# POWER.net
KiCad netlist of a schematic drawn in Altium Designer
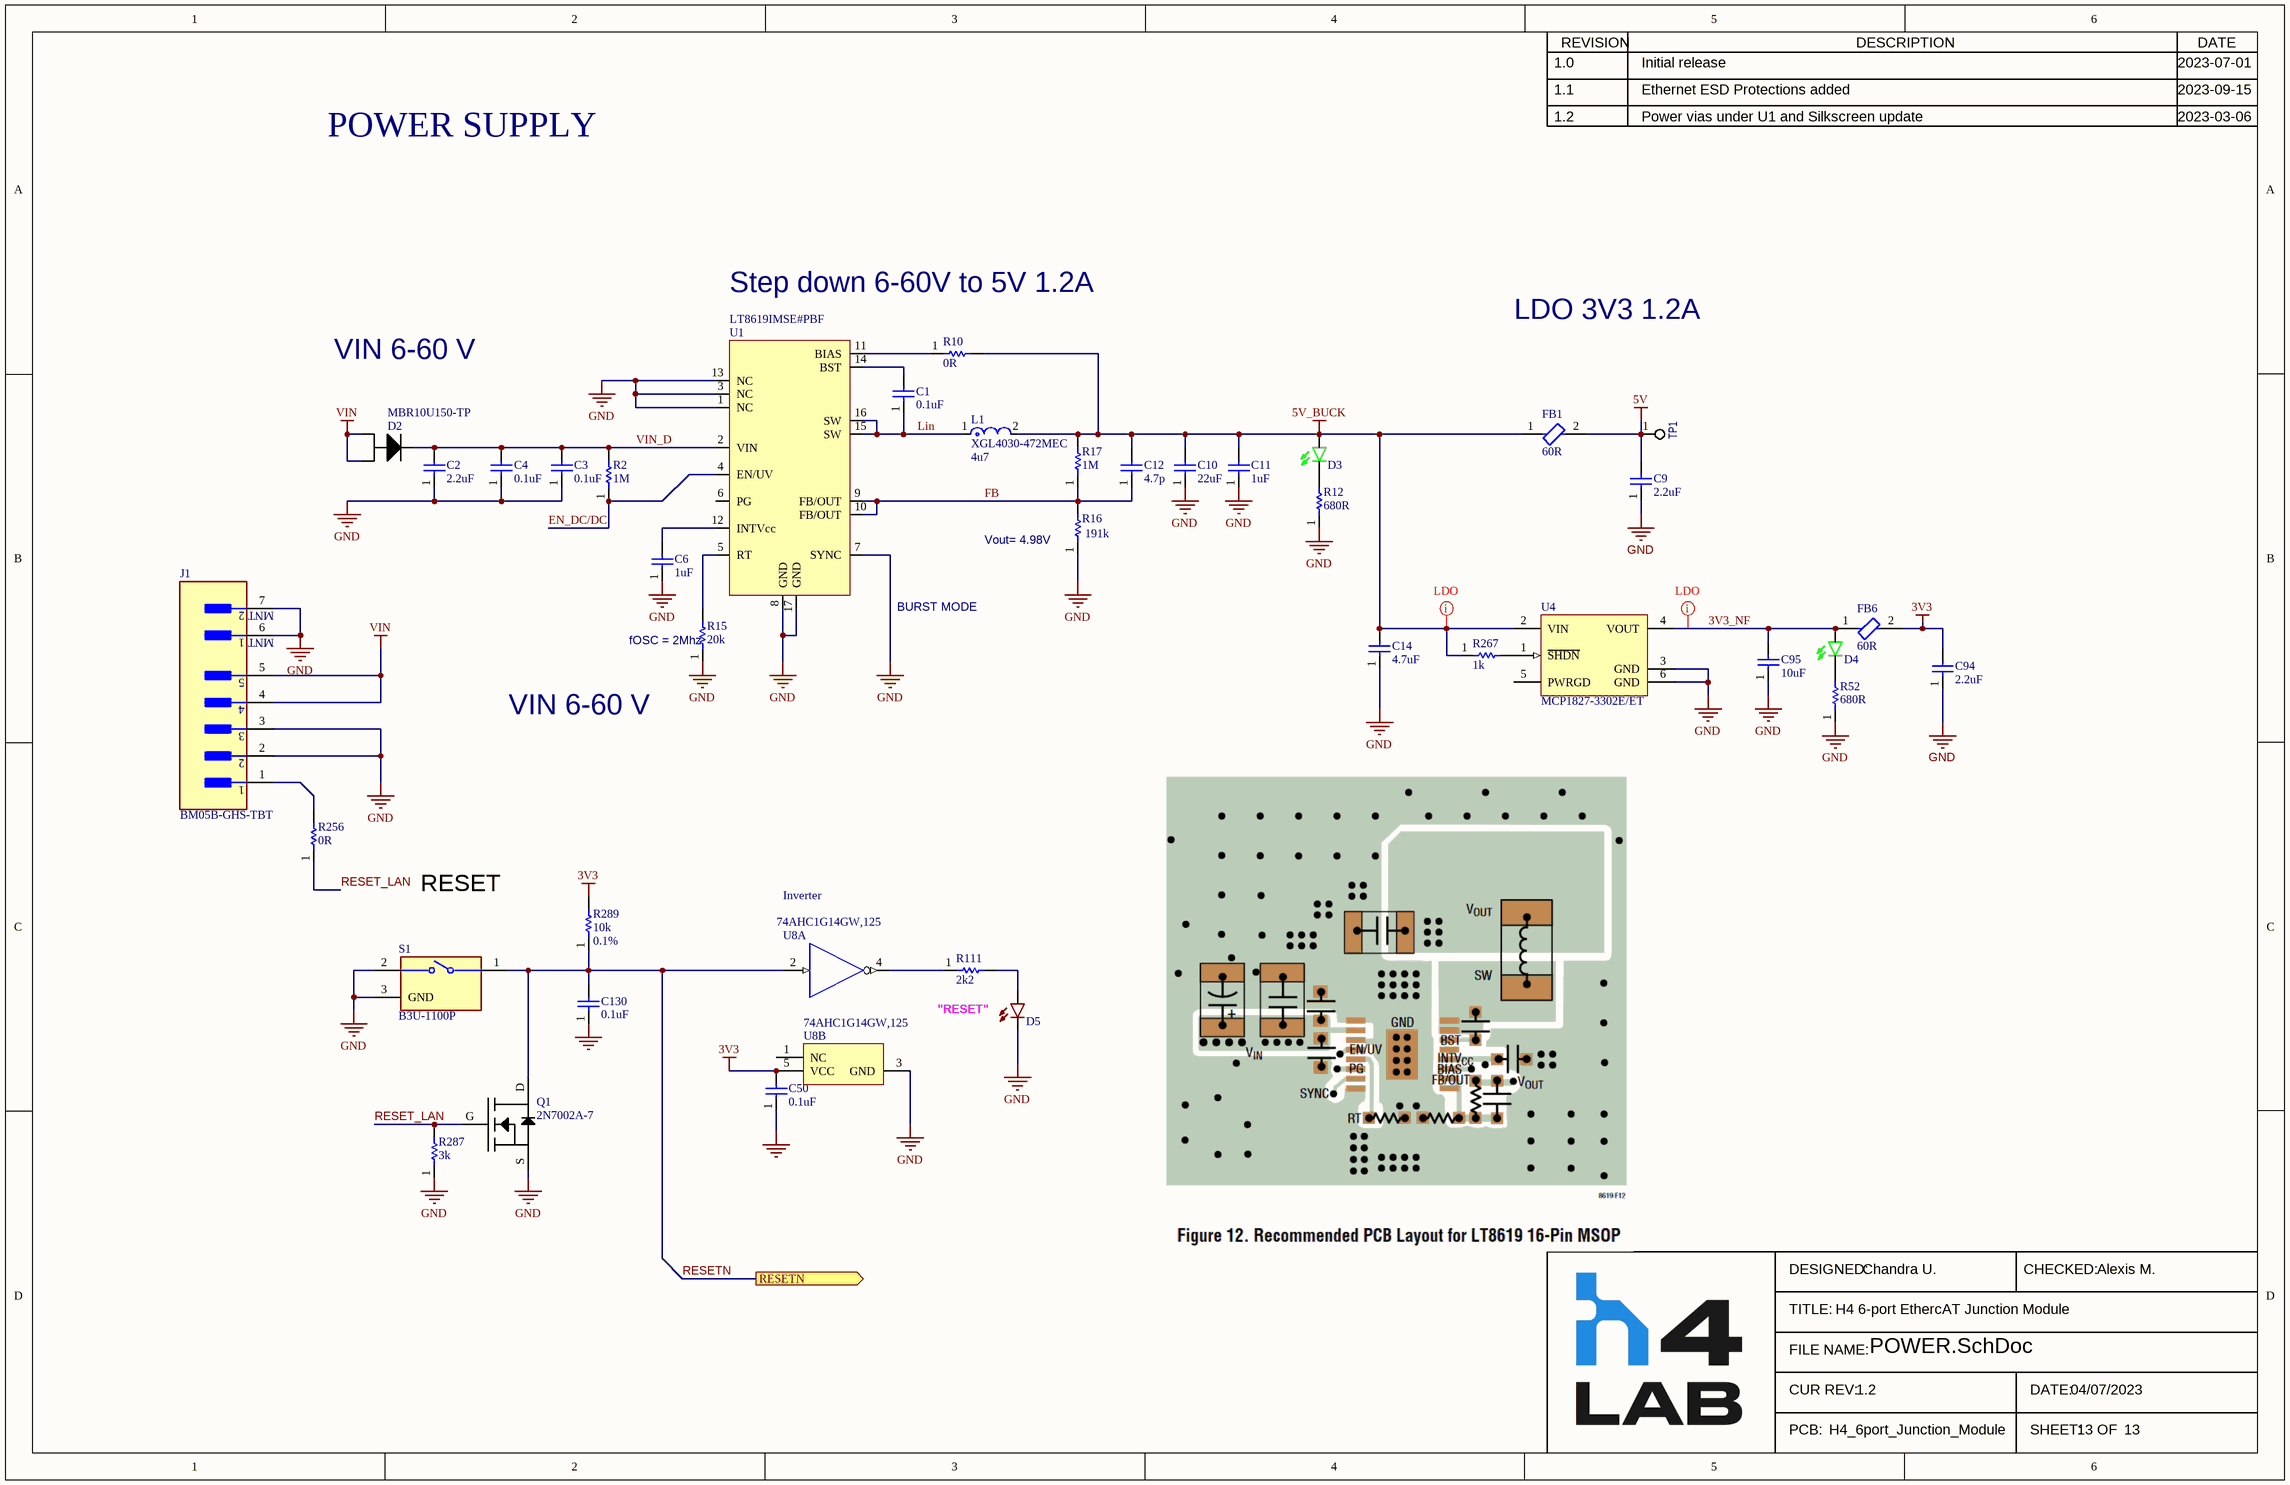
[diagram p0: POWER.SchDoc]

(export (version "E")
  (design (tool "Eeschema 10.0.6"))
  (components
    (comp (ref "C1")
      (value "0.1uF")
      (footprint "CAPC1608X09N(0603)")
      (description "CAP CER 0.1UF 100V X7R 0603")
      (fields (field (name "MPN") "CL10B104KC8NNNC") (field (name "TOLERANCE") "10%"))
      (libsource (lib "IHMC_Altium_Lib") (part "0.1uF_100V_0603_CAP"))
    )
    (comp (ref "C2")
      (value "2.2uF")
      (footprint "CAPC3216X16N(1206)")
      (description "CAP CER 2.2UF 100V X7S 1206")
      (fields (field (name "MPN") "C3216X7S2A225K160AB") (field (name "TOLERANCE") "10%"))
      (libsource (lib "IHMC_Altium_Lib") (part "2.2uF_100V_1206_Cap"))
    )
    (comp (ref "C3")
      (value "0.1uF")
      (footprint "CAPC1608X09N(0603)")
      (description "CAP CER 0.1UF 100V X7R 0603")
      (fields (field (name "MPN") "CL10B104KC8NNNC") (field (name "TOLERANCE") "10%"))
      (libsource (lib "IHMC_Altium_Lib") (part "0.1uF_100V_0603_CAP"))
    )
    (comp (ref "C4")
      (value "0.1uF")
      (footprint "CAPC1608X09N(0603)")
      (description "CAP CER 0.1UF 100V X7R 0603")
      (fields (field (name "MPN") "CL10B104KC8NNNC") (field (name "TOLERANCE") "10%"))
      (libsource (lib "IHMC_Altium_Lib") (part "0.1uF_100V_0603_CAP"))
    )
    (comp (ref "C6")
      (value "1uF")
      (footprint "CAPC1608X09N(0603)")
      (description "MLCC - SMD/SMT 25volts 1uF X5R 10%")
      (fields
        (field (name "MPN") "C0603C105K3PACTU")
        (field (name "VOLTAGE") "25VDC")
        (field (name "DRAWN BY") "TC")
      )
      (libsource (lib "IHMC_Altium_Lib") (part "1uF_25VDC_0603_Cap"))
    )
    (comp (ref "C9")
      (value "2.2uF")
      (footprint "CAPC1608X09N(0603)")
      (description "CAP CER 2.2UF 10V X5R 0603")
      (fields (field (name "MPN") "GRM188R61A225KE34D") (field (name "TOLERANCE") "10%"))
      (libsource (lib "IHMC_Altium_Lib") (part "2.2uF_10V_0603_CAP"))
    )
    (comp (ref "C10")
      (value "22uF")
      (footprint "CAPC1608X09N(0603)")
      (description "CAP CER 22UF 10V X5R 0603")
      (fields (field (name "MPN") "C1608X5R1A226M080AC") (field (name "TOLERANCE") "20%"))
      (libsource (lib "IHMC_Altium_Lib") (part "22uF_10V_0603_CAP"))
    )
    (comp (ref "C11")
      (value "1uF")
      (footprint "CAPC1608X09N(0603)")
      (description "MLCC - SMD/SMT 25volts 1uF X5R 10%")
      (fields
        (field (name "MPN") "C0603C105K3PACTU")
        (field (name "VOLTAGE") "25VDC")
        (field (name "DRAWN BY") "TC")
      )
      (libsource (lib "IHMC_Altium_Lib") (part "1uF_25VDC_0603_Cap"))
    )
    (comp (ref "C12")
      (value "4.7p")
      (footprint "0402_C")
      (fields
        (field (name "MANUFACTURER") "TDK")
        (field (name "MANUFACTURER PART NUMBER") "CGA2B2C0G1H4R7C050BA")
      )
      (libsource (lib "IHMC_Altium_Lib") (part "4p7_0402_50V_C0G_  CGA2B2C0G1H4R7C050BA"))
    )
    (comp (ref "C14")
      (value "4.7uF")
      (footprint "CAPC1608X09N(0603)")
      (description "CAP CER 4.7UF 10V X5R 0603")
      (fields (field (name "MPN") "CL10A475KP8NNNC"))
      (libsource (lib "IHMC_Altium_Lib") (part "4.7uF_10V_0603_CAP"))
    )
    (comp (ref "C50")
      (value "0.1uF")
      (footprint "CAPC1608X09N(0603)")
      (description "CAP CER 0.1UF 100V X7R 0603")
      (fields (field (name "MPN") "CL10B104KC8NNNC") (field (name "TOLERANCE") "10%"))
      (libsource (lib "IHMC_Altium_Lib") (part "0.1uF_100V_0603_CAP"))
    )
    (comp (ref "C94")
      (value "2.2uF")
      (footprint "CAPC1608X09N(0603)")
      (description "CAP CER 2.2UF 10V X5R 0603")
      (fields (field (name "MPN") "GRM188R61A225KE34D") (field (name "TOLERANCE") "10%"))
      (libsource (lib "IHMC_Altium_Lib") (part "2.2uF_10V_0603_CAP"))
    )
    (comp (ref "C95")
      (value "10uF")
      (footprint "CAPC3216X16N(1206)")
      (description "MLCC - SMD/SMT 1206 10uF 35volts")
      (fields
        (field (name "MPN") "GRM319R6YA106KA12D")
        (field (name "VOLTAGE") "35VDC")
        (field (name "DRAWN BY") "TC")
      )
      (libsource (lib "IHMC_Altium_Lib") (part "10uF_35VDC_1206_Cap"))
    )
    (comp (ref "C130")
      (value "0.1uF")
      (footprint "CAPC1608X09N(0603)")
      (description "CAP CER 0.1UF 100V X7R 0603")
      (fields (field (name "MPN") "CL10B104KC8NNNC") (field (name "TOLERANCE") "10%"))
      (libsource (lib "IHMC_Altium_Lib") (part "0.1uF_100V_0603_CAP"))
    )
    (comp (ref "D2")
      (value "MBR10U150-TP")
      (footprint "TO-277")
      (description "Diode Schottky 150V 10A TO277")
      (fields (field (name "MANUFACTURER") "MCC"))
      (libsource (lib "IHMC_Altium_Lib") (part "MBR10U150-TP_SCHOTTKY_150V_10A"))
    )
    (comp (ref "D3")
      (value "LTST-C193KGKT-5A")
      (footprint "LEDC1608X07N(0603)")
      (description "LED GREEN CLEAR CHIP SMD")
      (fields (field (name "DRAWN BY") "TC"))
      (libsource (lib "IHMC_Altium_Lib") (part "GREEN_LED_0603"))
    )
    (comp (ref "D4")
      (value "LTST-C193KGKT-5A")
      (footprint "LEDC1608X07N(0603)")
      (description "LED GREEN CLEAR CHIP SMD")
      (fields (field (name "DRAWN BY") "TC"))
      (libsource (lib "IHMC_Altium_Lib") (part "GREEN_LED_0603"))
    )
    (comp (ref "D5")
      (value "LTST-C193KRKT-5A")
      (footprint "LEDC1608X07N(0603)")
      (description "LED RED CLEAR CHIP SMD")
      (fields (field (name "DRAWN BY") "TC"))
      (libsource (lib "IHMC_Altium_Lib") (part "RED_LED_0603"))
    )
    (comp (ref "FB1")
      (value "BKP2125HS600-T")
      (footprint "FP-BKP2125-IPC_C")
      (fields
        (field (name "TOLERANCE") "25%")
        (field (name "MANUFACTURER") "Taiyo Yuden")
        (field (name "IMPEDANCE") "60R")
      )
      (libsource (lib "IHMC_Altium_Lib") (part "60R_100Mhz_0805_3A"))
    )
    (comp (ref "FB6")
      (value "BKP2125HS600-T")
      (footprint "FP-BKP2125-IPC_C")
      (fields
        (field (name "TOLERANCE") "25%")
        (field (name "MANUFACTURER") "Taiyo Yuden")
        (field (name "IMPEDANCE") "60R")
      )
      (libsource (lib "IHMC_Altium_Lib") (part "60R_100Mhz_0805_3A"))
    )
    (comp (ref "J1")
      (value "BM05B-GHS-TBT")
      (footprint "FP-BM05B-GHS-TBT_LF_SN-MFG")
      (description "GH Series 5 Circuits 1.25 mm Pitch Disconnectable Top Entry Shrouned Header")
      (fields
        (field (name "MANUFACTURER") "JST")
        (field (name "MANUFACTURER PART NUMBER") "BM05B-GHS-TBT(LF)(SN)(N)")
      )
      (libsource (lib "IHMC_Connector_Lib") (part "BM05B-GHS-TBT_5POS_JST_GH"))
    )
    (comp (ref "L1")
      (value "XGL4030-472MEC")
      (footprint "FP-XGL4030-472MEC-MFG")
      (description "Inductor Power Shielded Wirewound 4.7uH 20% 1MHz Composite 6.6A 31.5mOhm DCR Automotive T/R")
      (fields (field (name "ALTIUM_VALUE") "4u7") (field (name "MPN") "XGL4030-472"))
      (libsource (lib "IHMC_Altium_Lib") (part "XGL4030-472MEC_4u7_2A1_IND"))
    )
    (comp (ref "Q1")
      (value "2N7002A-7")
      (footprint "SOT95P230X110-3N")
      (description "MOSFET N-CH 60V 0.18A SOT23")
      (libsource (lib "IHMC_Altium_Lib") (part "2N7002_N-MOS"))
    )
    (comp (ref "R2")
      (value "1M")
      (footprint "RESC1608X09N(0603)")
      (description "RES SMD 1M OHM 1% 1/10W 0603")
      (fields (field (name "MPN") "RC0603FR-071ML") (field (name "TOLERANCE") "1%"))
      (libsource (lib "IHMC_Altium_Lib") (part "1M_1/10W_RES_0603"))
    )
    (comp (ref "R10")
      (value "0R")
      (footprint "RESC1608X09N(0603)")
      (description "RES SMD 0 OHM JUMPER 1/10W 0603")
      (fields (field (name "MPN") "RC0603JR-070RL") (field (name "TOLERANCE") "Jumper"))
      (libsource (lib "IHMC_Altium_Lib") (part "0R_1/10W_0603_RES"))
    )
    (comp (ref "R12")
      (value "680R")
      (footprint "RESC1608X09N(0603)")
      (description "RES SMD 680 OHM 1% 1/10W 0603")
      (fields (field (name "MPN") "RC0603FR-07680RL") (field (name "TOLERANCE") "1%"))
      (libsource (lib "IHMC_Altium_Lib") (part "680R_1/10W_0603_RES"))
    )
    (comp (ref "R15")
      (value "20k")
      (footprint "0402")
      (description "RES SMD 20K OHM 1% 1/10W 0402")
      (fields
        (field (name "MANUFACTURER") "Panasonic")
        (field (name "MANUFACTURER PART NUMBER") "ERJ-2RKF2002X")
      )
      (libsource (lib "IHMC_Altium_Lib") (part "20K_0402_1%_ERJ-2RKF2002X_RES"))
    )
    (comp (ref "R16")
      (value "191k")
      (footprint "0402")
      (description "Thick Film Resistors - SMD 0402 191Kohms 1% Tol")
      (fields (field (name "TOLERANCE") "1%") (field (name "MANUFACTURER") "Panasonic"))
      (libsource (lib "IHMC_Altium_Lib") (part "191k_0402_1%_ERJ-2RKF1913X"))
    )
    (comp (ref "R17")
      (value "1M")
      (footprint "RESC1608X09N(0603)")
      (description "RES SMD 1M OHM 1% 1/10W 0603")
      (fields (field (name "MPN") "RC0603FR-071ML") (field (name "TOLERANCE") "1%"))
      (libsource (lib "IHMC_Altium_Lib") (part "1M_1/10W_RES_0603"))
    )
    (comp (ref "R52")
      (value "680R")
      (footprint "RESC1608X09N(0603)")
      (description "RES SMD 680 OHM 1% 1/10W 0603")
      (fields (field (name "MPN") "RC0603FR-07680RL") (field (name "TOLERANCE") "1%"))
      (libsource (lib "IHMC_Altium_Lib") (part "680R_1/10W_0603_RES"))
    )
    (comp (ref "R111")
      (value "2k2")
      (footprint "RESC1608X09N(0603)")
      (description "RES SMD 2.2K OHM 1% 1/10W 0603")
      (fields (field (name "MPN") "RC0603FR-072K2L") (field (name "TOLERANCE") "1%"))
      (libsource (lib "IHMC_Altium_Lib") (part "2k2_1/10W_0603_RES"))
    )
    (comp (ref "R256")
      (value "0R")
      (footprint "RESC1608X09N(0603)")
      (description "RES SMD 0 OHM JUMPER 1/10W 0603")
      (fields (field (name "MPN") "RC0603JR-070RL") (field (name "TOLERANCE") "Jumper"))
      (libsource (lib "H4_6-port_EtherCAT_Junction_Module") (part "0R_1/10W_0603_RES"))
    )
    (comp (ref "R267")
      (value "1k")
      (footprint "RESC1608X09N(0603)")
      (description "MD 1/10watt 1.0Kohms 1%")
      (fields (field (name "MPN") "CRCW06031K00FKEA") (field (name "DRAWN BY") "TC"))
      (libsource (lib "IHMC_Altium_Lib") (part "1k_1/10W_RES_0603"))
    )
    (comp (ref "R287")
      (value "3k")
      (footprint "RESC1608X09N(0603)")
      (description "RES SMD 3K OHM 1% 1/10W 0603")
      (fields
        (field (name "MPN") "RC0603FR-073KL")
        (field (name "TOLERANCE") "1%")
        (field (name "DRAWN BY") "TC")
        (field (name "CHECKED BY") "*")
      )
      (libsource (lib "IHMC_Altium_Lib") (part "3k_1/10W_0603_RES"))
    )
    (comp (ref "R289")
      (value "10k")
      (footprint "0603")
      (description "RES SMD 10K OHM 0.1% 1/10W 0603")
      (fields
        (field (name "MANUFACTURER") "Yageo")
        (field (name "MANUFACTURER PART NUMBER") "RT0603BRB0710KL")
        (field (name "TOLERANCE") "0.1%")
      )
      (libsource (lib "IHMC_Altium_Lib") (part "10k_1/10W_0.1%_10ppm_0603_RES"))
    )
    (comp (ref "S1")
      (value "B3U-1100P")
      (footprint "FP-B3U-1100P-MFSWITCH_G")
      (description "Switch Tactile N.O. SPST Round Button Gull Wing 0.05A 12VDC 1.5N SMD Embossed T/R")
      (fields (field (name "MANUFACTURER") "Omron"))
      (libsource (lib "IHMC_Altium_Lib") (part "SWITCH_SPST_NO_B3U-1100P"))
    )
    (comp (ref "TP1")
      (value "TP_SMD")
      (footprint "Pad_1mm")
      (description "Test point SMD")
      (libsource (lib "H4_6-port_EtherCAT_Junction_Module") (part "TP_SMD_1MM"))
    )
    (comp (ref "U1")
      (value "LT8619IMSE#PBF")
      (footprint "SOP50P490X110-17N")
      (description "LT8619 - 60V, 1.2A Synchronous Monolithic Buck Regulator with 6µA Quiescent Current")
      (fields (field (name "MANUFACTURER") "Analog Devices / Linear Technology"))
      (libsource (lib "IHMC_Altium_Lib") (part "LT8619IMSE#PBF_BUCK_60V_1A2"))
    )
    (comp (ref "U4")
      (value "MCP1827-3302E/ET")
      (footprint "5-DDPAK _Model2")
      (description "MCP1827-3302E/ET; LDOVoltage Regulator; 1.5A; 3.3V +/-2%; 2.3 to 6Vin; 5-Pin D2PAK")
      (fields (field (name "MANUFACTURER") "Microchip"))
      (libsource (lib "IHMC_Converters_Regulators") (part "3V3_LDO_1A5_MCP1827-3302E/ET"))
    )
    (comp (ref "U8")
      (value "74AHC1G14GW,125")
      (footprint "NXP-SOT353-1_L_TSSOP5")
      (description "74AHC1G14GW/UMT5/REELR//")
      (fields
        (field (name "MANUFACTURER") "NXP Semiconductors")
        (field (name "MANUFACTURER PART NUMBER") "74AHC1G14GW125")
      )
      (libsource (lib "IHMC_Altium_Lib") (part "74AHC1G14GW,125_INVERTER_SCHMITT_5TSSOP"))
    )
  )
  (nets
    (net (code "1") (name "/3V3_NF") (class "Default")
      (node (ref "C95") (pin "2") (pinfunction "2_2") (pintype "passive"))
      (node (ref "D4") (pin "A") (pinfunction "A_A") (pintype "passive"))
      (node (ref "FB6") (pin "1") (pinfunction "1_1") (pintype "passive"))
      (node (ref "U4") (pin "4") (pinfunction "VOUT_4") (pintype "power_in"))
    )
    (net (code "2") (name "/EN_DC{slash}DC") (class "Default")
      (node (ref "R2") (pin "1") (pinfunction "1_1") (pintype "passive"))
      (node (ref "U1") (pin "4") (pinfunction "EN/UV_4") (pintype "passive"))
    )
    (net (code "3") (name "/FB") (class "Default")
      (node (ref "C12") (pin "1") (pinfunction "1_1") (pintype "passive"))
      (node (ref "R16") (pin "2") (pinfunction "2_2") (pintype "passive"))
      (node (ref "R17") (pin "1") (pinfunction "1_1") (pintype "passive"))
      (node (ref "U1") (pin "10") (pinfunction "FB/OUT_10") (pintype "passive"))
      (node (ref "U1") (pin "9") (pinfunction "FB/OUT_9") (pintype "passive"))
    )
    (net (code "4") (name "/Lin") (class "Default")
      (node (ref "C1") (pin "1") (pinfunction "1_1") (pintype "passive"))
      (node (ref "L1") (pin "1") (pinfunction "1_1") (pintype "passive"))
      (node (ref "U1") (pin "15") (pinfunction "SW_15") (pintype "passive"))
      (node (ref "U1") (pin "16") (pinfunction "SW_16") (pintype "passive"))
    )
    (net (code "5") (name "/RESETN") (class "Default")
      (node (ref "C130") (pin "2") (pinfunction "2_2") (pintype "passive"))
      (node (ref "Q1") (pin "D") (pinfunction "3_D") (pintype "passive"))
      (node (ref "R289") (pin "1") (pinfunction "1_1") (pintype "passive"))
      (node (ref "S1") (pin "1") (pinfunction "1_1") (pintype "passive"))
      (node (ref "U8") (pin "2") (pinfunction "A_2") (pintype "input"))
    )
    (net (code "6") (name "/RESET_LAN") (class "Default")
      (node (ref "Q1") (pin "G") (pinfunction "2_G") (pintype "passive"))
      (node (ref "R256") (pin "1") (pinfunction "1_1") (pintype "passive"))
      (node (ref "R287") (pin "2") (pinfunction "2_2") (pintype "passive"))
    )
    (net (code "7") (name "/VIN_D") (class "Default")
      (node (ref "C2") (pin "2") (pinfunction "2_2") (pintype "passive"))
      (node (ref "C3") (pin "2") (pinfunction "2_2") (pintype "passive"))
      (node (ref "C4") (pin "2") (pinfunction "2_2") (pintype "passive"))
      (node (ref "D2") (pin "3") (pinfunction "3_3") (pintype "passive"))
      (node (ref "R2") (pin "2") (pinfunction "2_2") (pintype "passive"))
      (node (ref "U1") (pin "2") (pinfunction "VIN_2") (pintype "passive"))
    )
    (net (code "8") (name "3V3") (class "Default")
      (node (ref "C50") (pin "2") (pinfunction "2_2") (pintype "passive"))
      (node (ref "C94") (pin "2") (pinfunction "2_2") (pintype "passive"))
      (node (ref "FB6") (pin "2") (pinfunction "2_2") (pintype "passive"))
      (node (ref "R289") (pin "2") (pinfunction "2_2") (pintype "passive"))
      (node (ref "U8") (pin "5") (pinfunction "VCC_5") (pintype "power_in"))
    )
    (net (code "9") (name "5V") (class "Default")
      (node (ref "C9") (pin "2") (pinfunction "2_2") (pintype "passive"))
      (node (ref "FB1") (pin "2") (pinfunction "2_2") (pintype "passive"))
      (node (ref "TP1") (pin "1") (pinfunction "IN_1") (pintype "passive"))
    )
    (net (code "10") (name "5V_BUCK") (class "Default")
      (node (ref "C10") (pin "2") (pinfunction "2_2") (pintype "passive"))
      (node (ref "C11") (pin "2") (pinfunction "2_2") (pintype "passive"))
      (node (ref "C12") (pin "2") (pinfunction "2_2") (pintype "passive"))
      (node (ref "C14") (pin "2") (pinfunction "2_2") (pintype "passive"))
      (node (ref "D3") (pin "A") (pinfunction "A_A") (pintype "passive"))
      (node (ref "FB1") (pin "1") (pinfunction "1_1") (pintype "passive"))
      (node (ref "L1") (pin "2") (pinfunction "2_2") (pintype "passive"))
      (node (ref "R10") (pin "2") (pinfunction "2_2") (pintype "passive"))
      (node (ref "R17") (pin "2") (pinfunction "2_2") (pintype "passive"))
      (node (ref "R267") (pin "1") (pinfunction "1_1") (pintype "passive"))
      (node (ref "U4") (pin "2") (pinfunction "VIN_2") (pintype "power_in"))
    )
    (net (code "11") (name "GND") (class "Default")
      (node (ref "C10") (pin "1") (pinfunction "1_1") (pintype "passive"))
      (node (ref "C11") (pin "1") (pinfunction "1_1") (pintype "passive"))
      (node (ref "C130") (pin "1") (pinfunction "1_1") (pintype "passive"))
      (node (ref "C14") (pin "1") (pinfunction "1_1") (pintype "passive"))
      (node (ref "C2") (pin "1") (pinfunction "1_1") (pintype "passive"))
      (node (ref "C3") (pin "1") (pinfunction "1_1") (pintype "passive"))
      (node (ref "C4") (pin "1") (pinfunction "1_1") (pintype "passive"))
      (node (ref "C50") (pin "1") (pinfunction "1_1") (pintype "passive"))
      (node (ref "C6") (pin "1") (pinfunction "1_1") (pintype "passive"))
      (node (ref "C9") (pin "1") (pinfunction "1_1") (pintype "passive"))
      (node (ref "C94") (pin "1") (pinfunction "1_1") (pintype "passive"))
      (node (ref "C95") (pin "1") (pinfunction "1_1") (pintype "passive"))
      (node (ref "D5") (pin "C") (pinfunction "C_C") (pintype "passive"))
      (node (ref "J1") (pin "2") (pinfunction "2_2") (pintype "passive"))
      (node (ref "J1") (pin "3") (pinfunction "3_3") (pintype "passive"))
      (node (ref "J1") (pin "6") (pinfunction "MNT_1_6") (pintype "passive"))
      (node (ref "J1") (pin "7") (pinfunction "MNT_2_7") (pintype "passive"))
      (node (ref "Q1") (pin "S") (pinfunction "1_S") (pintype "passive"))
      (node (ref "R12") (pin "1") (pinfunction "1_1") (pintype "passive"))
      (node (ref "R15") (pin "1") (pinfunction "1_1") (pintype "passive"))
      (node (ref "R16") (pin "1") (pinfunction "1_1") (pintype "passive"))
      (node (ref "R287") (pin "1") (pinfunction "1_1") (pintype "passive"))
      (node (ref "R52") (pin "1") (pinfunction "1_1") (pintype "passive"))
      (node (ref "S1") (pin "2") (pinfunction "2_2") (pintype "passive"))
      (node (ref "S1") (pin "3") (pinfunction "GND_3") (pintype "power_in"))
      (node (ref "U1") (pin "1") (pinfunction "NC_1") (pintype "passive"))
      (node (ref "U1") (pin "13") (pinfunction "NC_13") (pintype "passive"))
      (node (ref "U1") (pin "17") (pinfunction "GND_17") (pintype "passive"))
      (node (ref "U1") (pin "3") (pinfunction "NC_3") (pintype "passive"))
      (node (ref "U1") (pin "7") (pinfunction "SYNC_7") (pintype "passive"))
      (node (ref "U1") (pin "8") (pinfunction "GND_8") (pintype "passive"))
      (node (ref "U4") (pin "3") (pinfunction "GND_3") (pintype "power_in"))
      (node (ref "U4") (pin "6") (pinfunction "GND_6") (pintype "power_in"))
      (node (ref "U8") (pin "3") (pinfunction "GND_3") (pintype "power_in"))
    )
    (net (code "12") (name "Net-(D3-PadC)") (class "Default")
      (node (ref "D3") (pin "C") (pinfunction "C_C") (pintype "passive"))
      (node (ref "R12") (pin "2") (pinfunction "2_2") (pintype "passive"))
    )
    (net (code "13") (name "Net-(D4-PadC)") (class "Default")
      (node (ref "D4") (pin "C") (pinfunction "C_C") (pintype "passive"))
      (node (ref "R52") (pin "2") (pinfunction "2_2") (pintype "passive"))
    )
    (net (code "14") (name "Net-(D5-PadA)") (class "Default")
      (node (ref "D5") (pin "A") (pinfunction "A_A") (pintype "passive"))
      (node (ref "R111") (pin "2") (pinfunction "2_2") (pintype "passive"))
    )
    (net (code "15") (name "Net-(J1-Pad1)") (class "Default")
      (node (ref "J1") (pin "1") (pinfunction "1_1") (pintype "passive"))
      (node (ref "R256") (pin "2") (pinfunction "2_2") (pintype "passive"))
    )
    (net (code "16") (name "Net-(U1-BIAS)") (class "Default")
      (node (ref "R10") (pin "1") (pinfunction "1_1") (pintype "passive"))
      (node (ref "U1") (pin "11") (pinfunction "BIAS_11") (pintype "passive"))
    )
    (net (code "17") (name "Net-(U1-BST)") (class "Default")
      (node (ref "C1") (pin "2") (pinfunction "2_2") (pintype "passive"))
      (node (ref "U1") (pin "14") (pinfunction "BST_14") (pintype "passive"))
    )
    (net (code "18") (name "Net-(U1-INTVcc)") (class "Default")
      (node (ref "C6") (pin "2") (pinfunction "2_2") (pintype "passive"))
      (node (ref "U1") (pin "12") (pinfunction "INTVcc_12") (pintype "passive"))
    )
    (net (code "19") (name "Net-(U1-RT)") (class "Default")
      (node (ref "R15") (pin "2") (pinfunction "2_2") (pintype "passive"))
      (node (ref "U1") (pin "5") (pinfunction "RT_5") (pintype "passive"))
    )
    (net (code "20") (name "Net-(U4-~{SHDN})") (class "Default")
      (node (ref "R267") (pin "2") (pinfunction "2_2") (pintype "passive"))
      (node (ref "U4") (pin "1") (pinfunction "~{SHDN}_1") (pintype "input"))
    )
    (net (code "21") (name "Net-(U8A-~{Y})") (class "Default")
      (node (ref "R111") (pin "1") (pinfunction "1_1") (pintype "passive"))
      (node (ref "U8") (pin "4") (pinfunction "~{Y}_4") (pintype "output"))
    )
    (net (code "22") (name "VIN") (class "Default")
      (node (ref "D2") (pin "1") (pinfunction "1_1") (pintype "passive"))
      (node (ref "D2") (pin "2") (pinfunction "2_2") (pintype "passive"))
      (node (ref "J1") (pin "4") (pinfunction "4_4") (pintype "passive"))
      (node (ref "J1") (pin "5") (pinfunction "5_5") (pintype "passive"))
    )
    (net (code "23") (name "unconnected-(U1-PG-Pad6)") (class "Default")
      (node (ref "U1") (pin "6") (pinfunction "PG_6") (pintype "passive"))
    )
    (net (code "24") (name "unconnected-(U4-PWRGD-Pad5)") (class "Default")
      (node (ref "U4") (pin "5") (pinfunction "PWRGD_5") (pintype "power_in"))
    )
    (net (code "25") (name "unconnected-(U8B-NC-Pad1)") (class "Default")
      (node (ref "U8") (pin "1") (pinfunction "NC_1") (pintype "passive"))
    )
  )
)
